# 384X_PWMMOD.net
KiCad netlist of a schematic drawn in Altium Designer
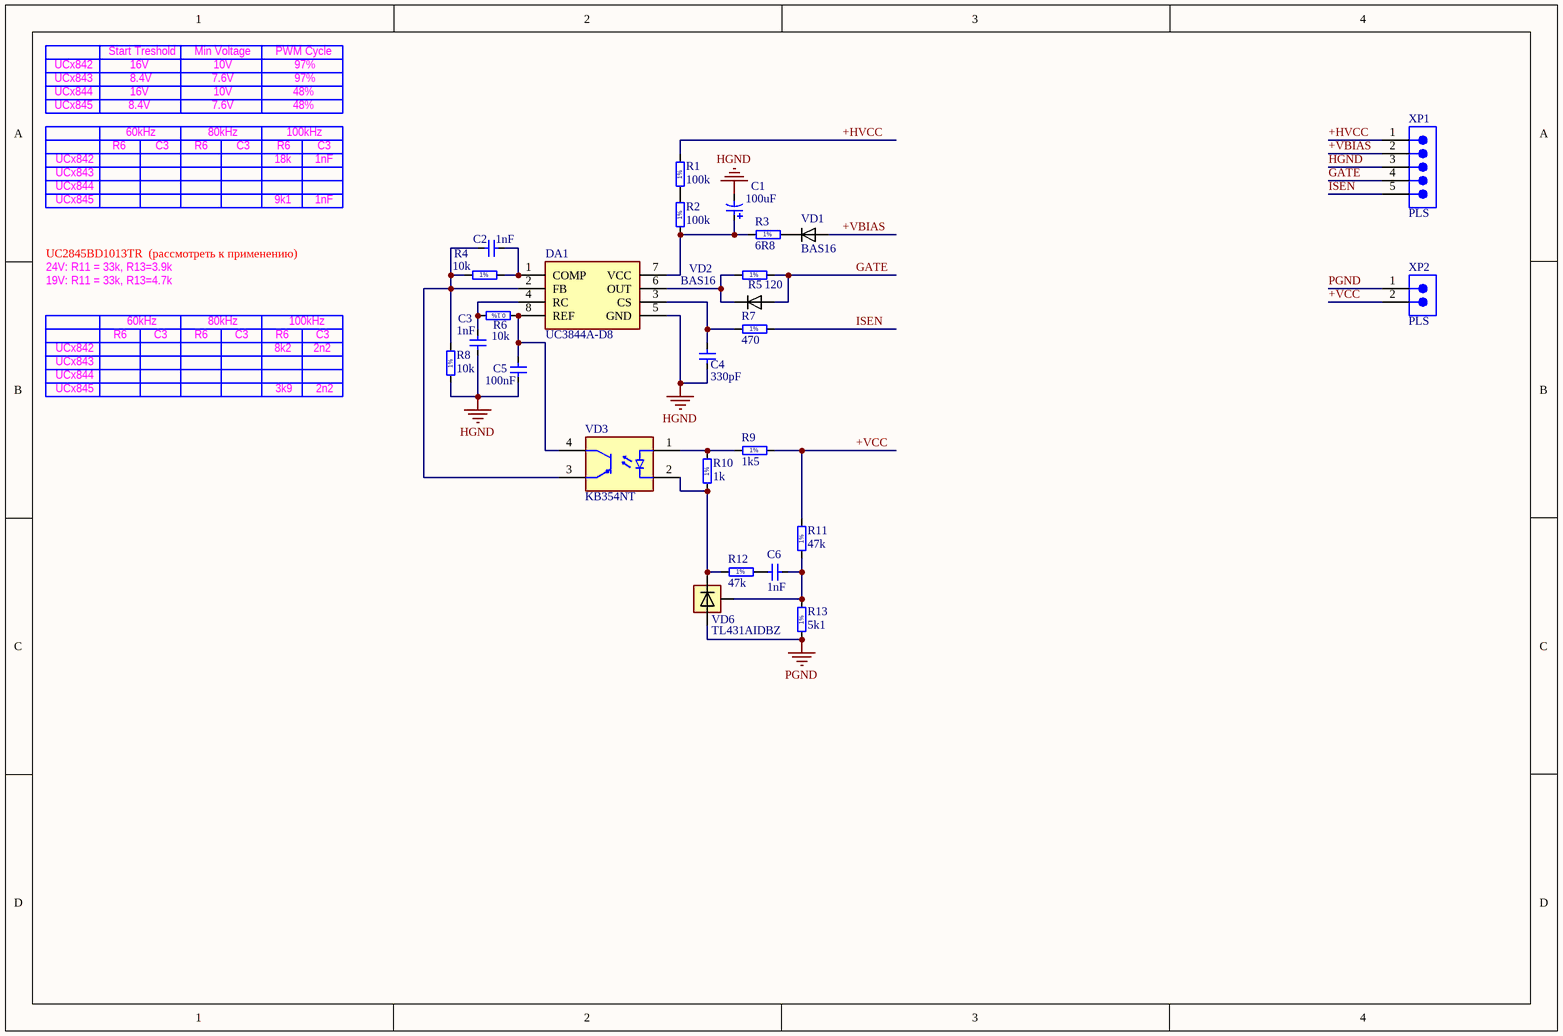
[diagram p0: 384X_PWMMOD.SchDoc]

(export (version "E")
  (design (tool "Eeschema 10.0.6"))
  (components
    (comp (ref "C1")
      (value "100uF")
      (footprint "CAP_EL_06_11_VERT")
      (fields (field (name "PART NUMBER") "SH016M0100BZF-0611 (VERT MOUNTED)") (field (name "VOLTAGE") "16V"))
      (libsource (lib "Capacitor") (part "CAP_POLAR"))
    )
    (comp (ref "C2")
      (value "1nF")
      (footprint "CAP0805R")
      (description "SMD 0805 Capacitor")
      (fields
        (field (name "PART NUMBER") "CC0805_1NF_50V_5%_X7R")
        (field (name "VOLTAGE") "50V")
        (field (name "AUTHOR") "I. Kuznetsov")
      )
      (libsource (lib "Capacitor") (part "CAP_NON_POLAR"))
    )
    (comp (ref "C3")
      (value "1nF")
      (footprint "CAP0805R")
      (description "SMD 0805 Capacitor")
      (fields
        (field (name "PART NUMBER") "CC0805_1NF_50V_5%_X7R")
        (field (name "VOLTAGE") "50V")
        (field (name "AUTHOR") "I. Kuznetsov")
      )
      (libsource (lib "Capacitor") (part "CAP_NON_POLAR"))
    )
    (comp (ref "C4")
      (value "330pF")
      (footprint "CAP0805R")
      (description "SMD 0805 Capacitor")
      (fields
        (field (name "PART NUMBER") "CC0805_330PF_50V_5%_NP0")
        (field (name "VOLTAGE") "50V")
        (field (name "AUTHOR") "I. Kuznetsov")
      )
      (libsource (lib "Capacitor") (part "CAP_NON_POLAR"))
    )
    (comp (ref "C5")
      (value "100nF")
      (footprint "CAP0805R")
      (description "SMD 0805 Capacitor")
      (fields
        (field (name "PART NUMBER") "CC0805_100NF_50V_10%_X7R")
        (field (name "VOLTAGE") "50V")
        (field (name "AUTHOR") "I. Kuznetsov")
      )
      (libsource (lib "Capacitor") (part "CAP_NON_POLAR"))
    )
    (comp (ref "C6")
      (value "1nF")
      (footprint "CAP0805R")
      (description "SMD 0805 Capacitor")
      (fields
        (field (name "PART NUMBER") "CC0805_1NF_50V_5%_X7R")
        (field (name "VOLTAGE") "50V")
        (field (name "AUTHOR") "I. Kuznetsov")
      )
      (libsource (lib "Capacitor") (part "CAP_NON_POLAR"))
    )
    (comp (ref "DA1")
      (value "UC3844A-D8")
      (footprint "SOP8")
      (libsource (lib "IC And Semiconductor") (part "UCX84X"))
    )
    (comp (ref "R1")
      (value "100k")
      (footprint "RES1206R")
      (fields
        (field (name "PART NUMBER") "R1206_100K_1%_0.25W_100PPM")
        (field (name "POWER") "0.25W")
        (field (name "TOLERANCE") "±1%")
        (field (name "AUTHOR") "CERN DEM JLC")
      )
      (libsource (lib "Resistor") (part "Resistor - 1%"))
    )
    (comp (ref "R2")
      (value "100k")
      (footprint "RES1206R")
      (fields
        (field (name "PART NUMBER") "R1206_100K_1%_0.25W_100PPM")
        (field (name "POWER") "0.25W")
        (field (name "TOLERANCE") "±1%")
        (field (name "AUTHOR") "CERN DEM JLC")
      )
      (libsource (lib "Resistor") (part "Resistor - 1%"))
    )
    (comp (ref "R3")
      (value "6R8")
      (footprint "RES0805R")
      (fields
        (field (name "PART NUMBER") "R0805_6R8_1%_0.125W_200PPM")
        (field (name "POWER") "0.125W")
        (field (name "TOLERANCE") "±1%")
        (field (name "AUTHOR") "CERN DEM JLC")
      )
      (libsource (lib "Resistor") (part "Resistor - 1%"))
    )
    (comp (ref "R4")
      (value "10k")
      (footprint "RES0805R")
      (fields
        (field (name "PART NUMBER") "R0805_10K_1%_0.125W_100PPM")
        (field (name "POWER") "0.125W")
        (field (name "TOLERANCE") "±1%")
        (field (name "AUTHOR") "CERN DEM JLC")
      )
      (libsource (lib "Resistor") (part "Resistor - 1%"))
    )
    (comp (ref "R5")
      (value "120")
      (footprint "RES0805R")
      (fields
        (field (name "PART NUMBER") "R0805_120R_1%_0.125W_100PPM")
        (field (name "POWER") "0.125W")
        (field (name "TOLERANCE") "±1%")
        (field (name "AUTHOR") "CERN DEM JLC")
      )
      (libsource (lib "Resistor") (part "Resistor - 1%"))
    )
    (comp (ref "R6")
      (value "10k")
      (footprint "RES0805R")
      (fields
        (field (name "PART NUMBER") "R0805_10K_0.1%_0.1W_10PPM")
        (field (name "POWER") "0.1W")
        (field (name "TOLERANCE") "±0.1%")
        (field (name "AUTHOR") "CERN DEM JLC")
      )
      (libsource (lib "Resistor") (part "Resistor - 0.1%"))
    )
    (comp (ref "R7")
      (value "470")
      (footprint "RES0805R")
      (fields
        (field (name "PART NUMBER") "R0805_470R_1%_0.125W_100PPM")
        (field (name "POWER") "0.125W")
        (field (name "TOLERANCE") "±1%")
        (field (name "AUTHOR") "CERN DEM JLC")
      )
      (libsource (lib "Resistor") (part "Resistor - 1%"))
    )
    (comp (ref "R8")
      (value "10k")
      (footprint "RES0805R")
      (fields
        (field (name "PART NUMBER") "R0805_10K_1%_0.125W_100PPM")
        (field (name "POWER") "0.125W")
        (field (name "TOLERANCE") "±1%")
        (field (name "AUTHOR") "CERN DEM JLC")
      )
      (libsource (lib "Resistor") (part "Resistor - 1%"))
    )
    (comp (ref "R9")
      (value "1k5")
      (footprint "RES0805R")
      (fields
        (field (name "PART NUMBER") "R0805_1K5_1%_0.125W_100PPM")
        (field (name "POWER") "0.125W")
        (field (name "TOLERANCE") "±1%")
        (field (name "AUTHOR") "CERN DEM JLC")
      )
      (libsource (lib "Resistor") (part "Resistor - 1%"))
    )
    (comp (ref "R10")
      (value "1k")
      (footprint "RES0805R")
      (fields
        (field (name "PART NUMBER") "R0805_1K_1%_0.125W_100PPM")
        (field (name "POWER") "0.125W")
        (field (name "TOLERANCE") "±1%")
        (field (name "AUTHOR") "CERN DEM JLC")
      )
      (libsource (lib "Resistor") (part "Resistor - 1%"))
    )
    (comp (ref "R11")
      (value "47k")
      (footprint "RES0805R")
      (fields
        (field (name "PART NUMBER") "R0805_47K_1%_0.125W_100PPM")
        (field (name "POWER") "0.125W")
        (field (name "TOLERANCE") "±1%")
        (field (name "AUTHOR") "CERN DEM JLC")
      )
      (libsource (lib "Resistor") (part "Resistor - 1%"))
    )
    (comp (ref "R12")
      (value "47k")
      (footprint "RES0805R")
      (fields
        (field (name "PART NUMBER") "R0805_47K_1%_0.125W_100PPM")
        (field (name "POWER") "0.125W")
        (field (name "TOLERANCE") "±1%")
        (field (name "AUTHOR") "CERN DEM JLC")
      )
      (libsource (lib "Resistor") (part "Resistor - 1%"))
    )
    (comp (ref "R13")
      (value "5k1")
      (footprint "RES0805R")
      (fields
        (field (name "PART NUMBER") "R0805_5K1_1%_0.125W_100PPM")
        (field (name "POWER") "0.125W")
        (field (name "TOLERANCE") "±1%")
        (field (name "AUTHOR") "CERN DEM JLC")
      )
      (libsource (lib "Resistor") (part "Resistor - 1%"))
    )
    (comp (ref "VD1")
      (value "BAS16")
      (footprint "SOT23")
      (description "Shottky Diode")
      (fields (field (name "PARTNUMBER") "BAS16"))
      (libsource (lib "tda2050") (part "BAS16"))
    )
    (comp (ref "VD2")
      (value "BAS16")
      (footprint "SOT23")
      (libsource (lib "IC And Semiconductor") (part "D_2P_SOT23"))
    )
    (comp (ref "VD3") (value "KB354NT") (footprint "SOP4") (libsource (lib "Optoelectronics") (part "xx817")))
    (comp (ref "VD6")
      (value "TL431AIDBZ")
      (footprint "SOT23")
      (libsource (lib "IC And Semiconductor") (part "Z_3P_SOT23"))
    )
    (comp (ref "XP1")
      (value "PLS")
      (footprint "PLS-05")
      (fields (field (name "PART NUMBER") "PLS-05") (field (name "MANUFACTURER") "AUK"))
      (libsource (lib "Connector") (part "CN_05P_1W"))
    )
    (comp (ref "XP2")
      (value "PLS")
      (footprint "PLS-02")
      (fields (field (name "PART NUMBER") "PLS-02") (field (name "MANUFACTURER") "AUK"))
      (libsource (lib "Connector") (part "CN_02P_1W"))
    )
  )
  (nets
    (net (code "1") (name "/+HVCC") (class "Default")
      (node (ref "R1") (pin "2") (pinfunction "2_2") (pintype "passive"))
      (node (ref "XP1") (pin "1") (pinfunction "1_1") (pintype "passive"))
    )
    (net (code "2") (name "/+VBIAS") (class "Default")
      (node (ref "VD1") (pin "1") (pinfunction "A_1") (pintype "passive"))
      (node (ref "XP1") (pin "2") (pinfunction "2_2") (pintype "passive"))
    )
    (net (code "3") (name "/+VCC") (class "Default")
      (node (ref "R11") (pin "2") (pinfunction "2_2") (pintype "passive"))
      (node (ref "R9") (pin "2") (pinfunction "2_2") (pintype "passive"))
      (node (ref "XP2") (pin "2") (pinfunction "2_2") (pintype "passive"))
    )
    (net (code "4") (name "/GATE") (class "Default")
      (node (ref "R5") (pin "2") (pinfunction "2_2") (pintype "passive"))
      (node (ref "VD2") (pin "1") (pinfunction "A_1") (pintype "passive"))
      (node (ref "XP1") (pin "4") (pinfunction "4_4") (pintype "passive"))
    )
    (net (code "5") (name "/ISEN") (class "Default")
      (node (ref "R7") (pin "2") (pinfunction "2_2") (pintype "passive"))
      (node (ref "XP1") (pin "5") (pinfunction "5_5") (pintype "passive"))
    )
    (net (code "6") (name "HGND") (class "Default")
      (node (ref "C1") (pin "2") (pinfunction "2_2") (pintype "passive"))
      (node (ref "C3") (pin "1") (pinfunction "1_1") (pintype "passive"))
      (node (ref "C4") (pin "1") (pinfunction "1_1") (pintype "passive"))
      (node (ref "C5") (pin "1") (pinfunction "1_1") (pintype "passive"))
      (node (ref "DA1") (pin "5") (pinfunction "GND_5") (pintype "passive"))
      (node (ref "R8") (pin "1") (pinfunction "1_1") (pintype "passive"))
      (node (ref "XP1") (pin "3") (pinfunction "3_3") (pintype "passive"))
    )
    (net (code "7") (name "Net-(C6-Pad1)") (class "Default")
      (node (ref "C6") (pin "1") (pinfunction "1_1") (pintype "passive"))
      (node (ref "R12") (pin "2") (pinfunction "2_2") (pintype "passive"))
    )
    (net (code "8") (name "Net-(DA1-COMP)") (class "Default")
      (node (ref "C2") (pin "2") (pinfunction "2_2") (pintype "passive"))
      (node (ref "DA1") (pin "1") (pinfunction "COMP_1") (pintype "passive"))
      (node (ref "R4") (pin "2") (pinfunction "2_2") (pintype "passive"))
    )
    (net (code "9") (name "Net-(DA1-CS)") (class "Default")
      (node (ref "C4") (pin "2") (pinfunction "2_2") (pintype "passive"))
      (node (ref "DA1") (pin "3") (pinfunction "CS_3") (pintype "passive"))
      (node (ref "R7") (pin "1") (pinfunction "1_1") (pintype "passive"))
    )
    (net (code "10") (name "Net-(DA1-FB)") (class "Default")
      (node (ref "C2") (pin "1") (pinfunction "1_1") (pintype "passive"))
      (node (ref "DA1") (pin "2") (pinfunction "FB_2") (pintype "passive"))
      (node (ref "R4") (pin "1") (pinfunction "1_1") (pintype "passive"))
      (node (ref "R8") (pin "2") (pinfunction "2_2") (pintype "passive"))
      (node (ref "VD3") (pin "3") (pinfunction "E_3") (pintype "passive"))
    )
    (net (code "11") (name "Net-(DA1-OUT)") (class "Default")
      (node (ref "DA1") (pin "6") (pinfunction "OUT_6") (pintype "passive"))
      (node (ref "R5") (pin "1") (pinfunction "1_1") (pintype "passive"))
      (node (ref "VD2") (pin "3") (pinfunction "K_3") (pintype "passive"))
    )
    (net (code "12") (name "Net-(DA1-RC)") (class "Default")
      (node (ref "C3") (pin "2") (pinfunction "2_2") (pintype "passive"))
      (node (ref "DA1") (pin "4") (pinfunction "RC_4") (pintype "passive"))
      (node (ref "R6") (pin "2") (pinfunction "2_2") (pintype "passive"))
    )
    (net (code "13") (name "Net-(DA1-REF)") (class "Default")
      (node (ref "C5") (pin "2") (pinfunction "2_2") (pintype "passive"))
      (node (ref "DA1") (pin "8") (pinfunction "REF_8") (pintype "passive"))
      (node (ref "R6") (pin "1") (pinfunction "1_1") (pintype "passive"))
      (node (ref "VD3") (pin "4") (pinfunction "C_4") (pintype "passive"))
    )
    (net (code "14") (name "Net-(DA1-VCC)") (class "Default")
      (node (ref "C1") (pin "1") (pinfunction "1_1") (pintype "passive"))
      (node (ref "DA1") (pin "7") (pinfunction "VCC_7") (pintype "passive"))
      (node (ref "R2") (pin "1") (pinfunction "1_1") (pintype "passive"))
      (node (ref "R3") (pin "1") (pinfunction "1_1") (pintype "passive"))
    )
    (net (code "15") (name "Net-(R1-Pad1)") (class "Default")
      (node (ref "R1") (pin "1") (pinfunction "1_1") (pintype "passive"))
      (node (ref "R2") (pin "2") (pinfunction "2_2") (pintype "passive"))
    )
    (net (code "16") (name "Net-(R10-Pad2)") (class "Default")
      (node (ref "R10") (pin "2") (pinfunction "2_2") (pintype "passive"))
      (node (ref "R9") (pin "1") (pinfunction "1_1") (pintype "passive"))
      (node (ref "VD3") (pin "1") (pinfunction "1_1") (pintype "passive"))
    )
    (net (code "17") (name "Net-(VD1-K)") (class "Default")
      (node (ref "R3") (pin "2") (pinfunction "2_2") (pintype "passive"))
      (node (ref "VD1") (pin "3") (pinfunction "K_3") (pintype "passive"))
    )
    (net (code "18") (name "Net-(VD6-K)") (class "Default")
      (node (ref "R10") (pin "1") (pinfunction "1_1") (pintype "passive"))
      (node (ref "R12") (pin "1") (pinfunction "1_1") (pintype "passive"))
      (node (ref "VD3") (pin "2") (pinfunction "2_2") (pintype "passive"))
      (node (ref "VD6") (pin "1") (pinfunction "K_1") (pintype "passive"))
    )
    (net (code "19") (name "Net-(VD6-REF)") (class "Default")
      (node (ref "C6") (pin "2") (pinfunction "2_2") (pintype "passive"))
      (node (ref "R11") (pin "1") (pinfunction "1_1") (pintype "passive"))
      (node (ref "R13") (pin "2") (pinfunction "2_2") (pintype "passive"))
      (node (ref "VD6") (pin "2") (pinfunction "REF_2") (pintype "passive"))
    )
    (net (code "20") (name "PGND") (class "Default")
      (node (ref "R13") (pin "1") (pinfunction "1_1") (pintype "passive"))
      (node (ref "VD6") (pin "3") (pinfunction "A_3") (pintype "passive"))
      (node (ref "XP2") (pin "1") (pinfunction "1_1") (pintype "passive"))
    )
  )
)
